# ProPrj_Pocket_bot_2026-03-04.net
KiCad netlist of a schematic drawn in EasyEDA Pro
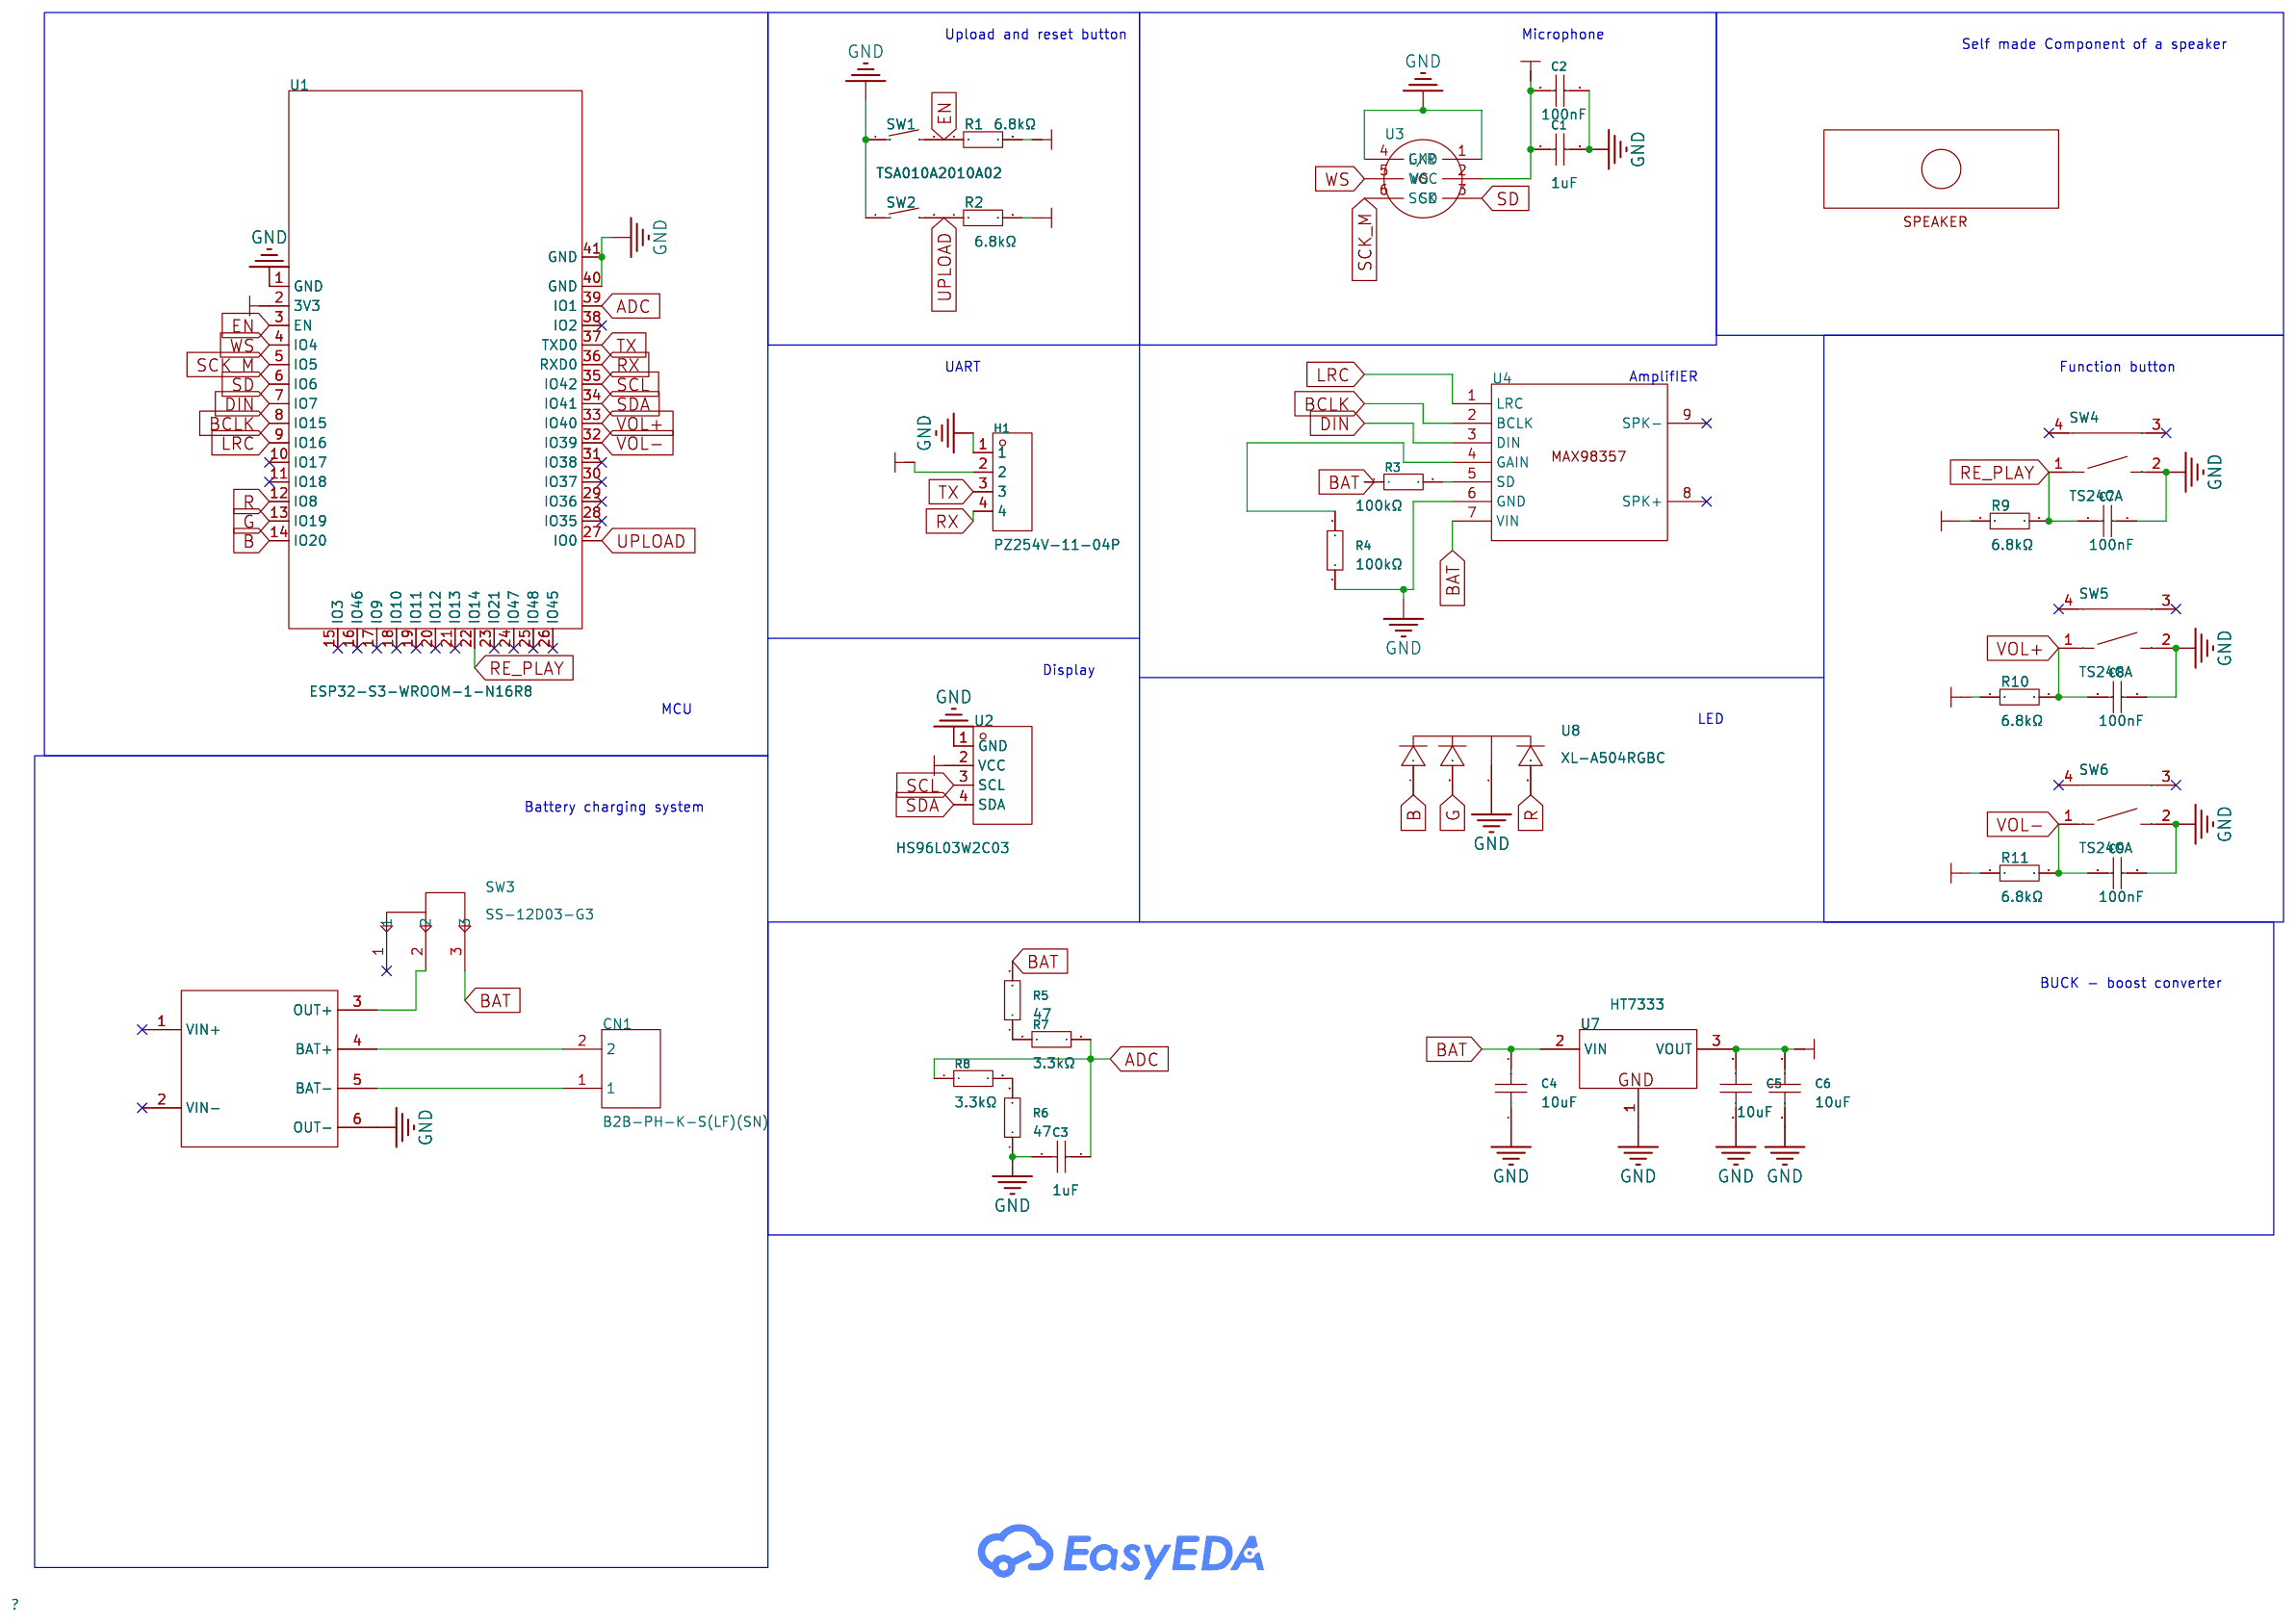
[diagram p0: schematic sheet]

(export (version "E")
  (design (tool "Eeschema 10.0.6"))
  (components
    (comp (ref "C1")
      (value "1uF")
      (footprint "easyedapro:C0805")
      (description "Capacitance:1uF Tolerance:±10% Tolerance:±10% Voltage Rating:50V Temperature Coefficient:X7R")
      (fields
        (field (name "Manufacturer Part") "CL21B105KBFNNNE")
        (field (name "Manufacturer") "SAMSUNG(三星)")
      )
      (libsource (lib "easyedapro") (part "CL21B105KBFNNNE"))
    )
    (comp (ref "C2")
      (value "100nF")
      (footprint "easyedapro:C1206")
      (description "Capacitance:100nF Tolerance:±10% Tolerance:±10% Voltage Rating:50V Temperature Coefficient:X7R")
      (fields
        (field (name "Manufacturer Part") "CL31B104KBCNNNC")
        (field (name "Manufacturer") "SAMSUNG(三星)")
      )
      (libsource (lib "easyedapro") (part "CL31B104KBCNNNC"))
    )
    (comp (ref "C3")
      (value "1uF")
      (footprint "easyedapro:C0805")
      (description "Capacitance:1uF Tolerance:±10% Tolerance:±10% Voltage Rating:50V Temperature Coefficient:X7R")
      (fields
        (field (name "Manufacturer Part") "CL21B105KBFNNNE")
        (field (name "Manufacturer") "SAMSUNG(三星)")
      )
      (libsource (lib "easyedapro") (part "CL21B105KBFNNNE"))
    )
    (comp (ref "C4")
      (value "10uF")
      (footprint "easyedapro:C0603")
      (description "Capacitance:10uF Tolerance:±20% Tolerance:±20% Voltage Rating:25V Temperature Coefficient:X5R")
      (fields
        (field (name "Manufacturer Part") "CL10A106MA8NRNC")
        (field (name "Manufacturer") "SAMSUNG(三星)")
      )
      (libsource (lib "easyedapro") (part "CL10A106MA8NRNC"))
    )
    (comp (ref "C5")
      (value "10uF")
      (footprint "easyedapro:C0603")
      (description "Capacitance:10uF Tolerance:±20% Tolerance:±20% Voltage Rating:25V Temperature Coefficient:X5R")
      (fields
        (field (name "Manufacturer Part") "CL10A106MA8NRNC")
        (field (name "Manufacturer") "SAMSUNG(三星)")
      )
      (libsource (lib "easyedapro") (part "CL10A106MA8NRNC"))
    )
    (comp (ref "C6")
      (value "10uF")
      (footprint "easyedapro:C0603")
      (description "Capacitance:10uF Tolerance:±20% Tolerance:±20% Voltage Rating:25V Temperature Coefficient:X5R")
      (fields
        (field (name "Manufacturer Part") "CL10A106MA8NRNC")
        (field (name "Manufacturer") "SAMSUNG(三星)")
      )
      (libsource (lib "easyedapro") (part "CL10A106MA8NRNC"))
    )
    (comp (ref "C7")
      (value "100nF")
      (footprint "easyedapro:C1206")
      (description "Capacitance:100nF Tolerance:±10% Tolerance:±10% Voltage Rating:50V Temperature Coefficient:X7R")
      (fields
        (field (name "Manufacturer Part") "CL31B104KBCNNNC")
        (field (name "Manufacturer") "SAMSUNG(三星)")
      )
      (libsource (lib "easyedapro") (part "CL31B104KBCNNNC"))
    )
    (comp (ref "C8")
      (value "100nF")
      (footprint "easyedapro:C1206")
      (description "Capacitance:100nF Tolerance:±10% Tolerance:±10% Voltage Rating:50V Temperature Coefficient:X7R")
      (fields
        (field (name "Manufacturer Part") "CL31B104KBCNNNC")
        (field (name "Manufacturer") "SAMSUNG(三星)")
      )
      (libsource (lib "easyedapro") (part "CL31B104KBCNNNC"))
    )
    (comp (ref "C9")
      (value "100nF")
      (footprint "easyedapro:C1206")
      (description "Capacitance:100nF Tolerance:±10% Tolerance:±10% Voltage Rating:50V Temperature Coefficient:X7R")
      (fields
        (field (name "Manufacturer Part") "CL31B104KBCNNNC")
        (field (name "Manufacturer") "SAMSUNG(三星)")
      )
      (libsource (lib "easyedapro") (part "CL31B104KBCNNNC"))
    )
    (comp (ref "CN1")
      (value "B2B-PH-K-S(LF)(SN)")
      (footprint "easyedapro:CONN-TH_B2B-PH-K-S")
      (fields (field (name "Manufacturer") "JST"))
      (libsource (lib "easyedapro") (part "B2B-PH-K-S(LF)(SN)"))
    )
    (comp (ref "H1")
      (value "PZ254V-11-04P")
      (footprint "easyedapro:HDR-TH_4P-P2.54-V-M")
      (fields (field (name "Manufacturer") "XFCN(兴飞)"))
      (libsource (lib "easyedapro") (part "PZ254V-11-04P_C2691448"))
    )
    (comp (ref "R1")
      (value "6.8kΩ")
      (footprint "easyedapro:R0603")
      (fields (field (name "Manufacturer Part") "RC0603FR-071KL") (field (name "Manufacturer") "YAGEO(国巨)"))
      (libsource (lib "easyedapro") (part "RC0603FR-071KL"))
    )
    (comp (ref "R2")
      (value "6.8kΩ")
      (footprint "easyedapro:R0603")
      (fields (field (name "Manufacturer Part") "RC0603FR-071KL") (field (name "Manufacturer") "YAGEO(国巨)"))
      (libsource (lib "easyedapro") (part "RC0603FR-071KL"))
    )
    (comp (ref "R3")
      (value "100kΩ")
      (footprint "easyedapro:R0603")
      (fields (field (name "Manufacturer Part") "RC0603FR-07100KL") (field (name "Manufacturer") "YAGEO(国巨)"))
      (libsource (lib "easyedapro") (part "RC0603FR-07100KL"))
    )
    (comp (ref "R4")
      (value "100kΩ")
      (footprint "easyedapro:R0603")
      (fields (field (name "Manufacturer Part") "RC0603FR-07100KL") (field (name "Manufacturer") "YAGEO(国巨)"))
      (libsource (lib "easyedapro") (part "RC0603FR-07100KL"))
    )
    (comp (ref "R5")
      (value "47")
      (footprint "easyedapro:R1206")
      (fields
        (field (name "Manufacturer Part") "1206W4F100KT5E")
        (field (name "Manufacturer") "UNI-ROYAL(厚声)")
      )
      (libsource (lib "easyedapro") (part "1206W4F100KT5E"))
    )
    (comp (ref "R6")
      (value "47")
      (footprint "easyedapro:R1206")
      (fields
        (field (name "Manufacturer Part") "1206W4F100KT5E")
        (field (name "Manufacturer") "UNI-ROYAL(厚声)")
      )
      (libsource (lib "easyedapro") (part "1206W4F100KT5E"))
    )
    (comp (ref "R7")
      (value "3.3kΩ")
      (footprint "easyedapro:R0603")
      (fields
        (field (name "Manufacturer Part") "0603WAF3301T5E")
        (field (name "Manufacturer") "UNI-ROYAL(厚声)")
      )
      (libsource (lib "easyedapro") (part "0603WAF3301T5E"))
    )
    (comp (ref "R8")
      (value "3.3kΩ")
      (footprint "easyedapro:R0603")
      (fields
        (field (name "Manufacturer Part") "0603WAF3301T5E")
        (field (name "Manufacturer") "UNI-ROYAL(厚声)")
      )
      (libsource (lib "easyedapro") (part "0603WAF3301T5E"))
    )
    (comp (ref "R9")
      (value "6.8kΩ")
      (footprint "easyedapro:R0603")
      (fields (field (name "Manufacturer Part") "RC0603FR-071KL") (field (name "Manufacturer") "YAGEO(国巨)"))
      (libsource (lib "easyedapro") (part "RC0603FR-071KL"))
    )
    (comp (ref "R10")
      (value "6.8kΩ")
      (footprint "easyedapro:R0603")
      (fields (field (name "Manufacturer Part") "RC0603FR-071KL") (field (name "Manufacturer") "YAGEO(国巨)"))
      (libsource (lib "easyedapro") (part "RC0603FR-071KL"))
    )
    (comp (ref "R11")
      (value "6.8kΩ")
      (footprint "easyedapro:R0603")
      (fields (field (name "Manufacturer Part") "RC0603FR-071KL") (field (name "Manufacturer") "YAGEO(国巨)"))
      (libsource (lib "easyedapro") (part "RC0603FR-071KL"))
    )
    (comp (ref "SW1")
      (value "TSA010A2010A02")
      (footprint "easyedapro:KEY-SMD_L3.9-W3.0-LS5.0")
      (fields (field (name "Manufacturer") "BZCN(博众电气)"))
      (libsource (lib "easyedapro") (part "TSA010A2010A02"))
    )
    (comp (ref "SW2")
      (value "TSA010A2010A02")
      (footprint "easyedapro:KEY-SMD_L3.9-W3.0-LS5.0")
      (fields (field (name "Manufacturer") "BZCN(博众电气)"))
      (libsource (lib "easyedapro") (part "TSA010A2010A02"))
    )
    (comp (ref "SW3")
      (value "SS-12D03-G3")
      (footprint "easyedapro:SW-TH_3P-L8.5-W3.5-P2.50_SS-12D03-G3_C5160828")
      (fields (field (name "Manufacturer") "DEALON(德艺隆)"))
      (libsource (lib "easyedapro") (part "SS-12D03-G3_C5160828"))
    )
    (comp (ref "SW4")
      (value "TS24CA")
      (footprint "easyedapro:SW-SMD_2P-TS24CA")
      (fields (field (name "Manufacturer") "SHOU HAN(首韩)"))
      (libsource (lib "easyedapro") (part "TS24CA"))
    )
    (comp (ref "SW5")
      (value "TS24CA")
      (footprint "easyedapro:SW-SMD_2P-TS24CA")
      (fields (field (name "Manufacturer") "SHOU HAN(首韩)"))
      (libsource (lib "easyedapro") (part "TS24CA"))
    )
    (comp (ref "SW6")
      (value "TS24CA")
      (footprint "easyedapro:SW-SMD_2P-TS24CA")
      (fields (field (name "Manufacturer") "SHOU HAN(首韩)"))
      (libsource (lib "easyedapro") (part "TS24CA"))
    )
    (comp (ref "U1")
      (value "ESP32-S3-WROOM-1-N16R8")
      (footprint "easyedapro:WIRELM-SMD_ESP32-S3-WROOM-1")
      (fields (field (name "Manufacturer") "ESPRESSIF(乐鑫)"))
      (libsource (lib "easyedapro") (part "ESP32-S3-WROOM-1(N16R8)"))
    )
    (comp (ref "U2")
      (value "HS96L03W2C03")
      (footprint "easyedapro:OLED-TH_L27.8-W27.2-P2.54_C9900033791")
      (fields (field (name "Manufacturer") "HS(汉昇)"))
      (libsource (lib "easyedapro") (part "HS96L03W2C03"))
    )
    (comp (ref "U3")
      (value "~")
      (footprint "easyedapro:INMP441")
      (libsource (lib "easyedapro") (part "INMP441"))
    )
    (comp (ref "U4")
      (value "~")
      (footprint "easyedapro:MAX98357")
      (libsource (lib "easyedapro") (part "MAX98357"))
    )
    (comp (ref "U5")
      (value "~")
      (footprint "easyedapro:SPEAKER")
      (libsource (lib "easyedapro") (part "SPEAKER"))
    )
    (comp (ref "U6")
      (value "~")
      (footprint "easyedapro:TP4056 Carging Module")
      (libsource (lib "easyedapro") (part "TP4056 Charging Module"))
    )
    (comp (ref "U7")
      (value "HT7333")
      (footprint "easyedapro:SOT-89-3_L4.5-W2.5-P1.50-LS4.1-BR")
      (description "Output Type:-")
      (libsource (lib "easyedapro") (part "HT7333"))
    )
    (comp (ref "U8")
      (value "XL-A504RGBC")
      (footprint "easyedapro:LED-TH_4P-BD5.8-P1.25_DM-50346EH-73826CC-05RGB-BML60-D")
      (fields (field (name "Manufacturer") "XINGLIGHT(成兴光)"))
      (libsource (lib "easyedapro") (part "XL-A504RGBC"))
    )
  )
  (nets
    (net (code "1") (name "+3V3") (class "Default")
      (node (ref "C1") (pin "1") (pinfunction "1_1") (pintype "input"))
      (node (ref "C2") (pin "1") (pinfunction "1_1") (pintype "input"))
      (node (ref "C5") (pin "2") (pinfunction "2_2") (pintype "input"))
      (node (ref "C6") (pin "2") (pinfunction "2_2") (pintype "input"))
      (node (ref "H1") (pin "2") (pinfunction "2_2") (pintype "input"))
      (node (ref "R1") (pin "2") (pinfunction "2_2") (pintype "input"))
      (node (ref "R10") (pin "2") (pinfunction "2_2") (pintype "input"))
      (node (ref "R11") (pin "2") (pinfunction "2_2") (pintype "input"))
      (node (ref "R2") (pin "2") (pinfunction "2_2") (pintype "input"))
      (node (ref "R9") (pin "2") (pinfunction "2_2") (pintype "input"))
      (node (ref "U1") (pin "2") (pinfunction "3V3_2") (pintype "unspecified"))
      (node (ref "U2") (pin "2") (pinfunction "VCC_2") (pintype "unspecified"))
      (node (ref "U3") (pin "2") (pinfunction "VCC_2") (pintype "input"))
      (node (ref "U7") (pin "3") (pinfunction "VOUT_3") (pintype "unspecified"))
    )
    (net (code "2") (name "ADC") (class "Default")
      (node (ref "C3") (pin "2") (pinfunction "2_2") (pintype "input"))
      (node (ref "R7") (pin "2") (pinfunction "2_2") (pintype "input"))
      (node (ref "R8") (pin "1") (pinfunction "1_1") (pintype "input"))
      (node (ref "U1") (pin "39") (pinfunction "IO1_39") (pintype "unspecified"))
    )
    (net (code "3") (name "B") (class "Default")
      (node (ref "U1") (pin "14") (pinfunction "IO20_14") (pintype "unspecified"))
      (node (ref "U8") (pin "4") (pinfunction "4_4") (pintype "unspecified"))
    )
    (net (code "4") (name "BAT") (class "Default")
      (node (ref "C4") (pin "2") (pinfunction "2_2") (pintype "input"))
      (node (ref "R3") (pin "1") (pinfunction "1_1") (pintype "input"))
      (node (ref "R5") (pin "2") (pinfunction "2_2") (pintype "input"))
      (node (ref "SW3") (pin "3") (pinfunction "3_3") (pintype "unspecified"))
      (node (ref "U4") (pin "7") (pinfunction "VIN_7") (pintype "input"))
      (node (ref "U7") (pin "2") (pinfunction "VIN_2") (pintype "unspecified"))
    )
    (net (code "5") (name "BCLK") (class "Default")
      (node (ref "U1") (pin "8") (pinfunction "IO15_8") (pintype "unspecified"))
      (node (ref "U4") (pin "2") (pinfunction "BCLK_2") (pintype "input"))
    )
    (net (code "6") (name "DIN") (class "Default")
      (node (ref "U1") (pin "7") (pinfunction "IO7_7") (pintype "unspecified"))
      (node (ref "U4") (pin "3") (pinfunction "DIN_3") (pintype "input"))
    )
    (net (code "7") (name "EN") (class "Default")
      (node (ref "R1") (pin "1") (pinfunction "1_1") (pintype "input"))
      (node (ref "SW1") (pin "2") (pinfunction "2_2") (pintype "unspecified"))
      (node (ref "U1") (pin "3") (pinfunction "EN_3") (pintype "unspecified"))
    )
    (net (code "8") (name "G") (class "Default")
      (node (ref "U1") (pin "13") (pinfunction "IO19_13") (pintype "unspecified"))
      (node (ref "U8") (pin "3") (pinfunction "3_3") (pintype "unspecified"))
    )
    (net (code "9") (name "GND") (class "Default")
      (node (ref "C1") (pin "2") (pinfunction "2_2") (pintype "input"))
      (node (ref "C2") (pin "2") (pinfunction "2_2") (pintype "input"))
      (node (ref "C3") (pin "1") (pinfunction "1_1") (pintype "input"))
      (node (ref "C4") (pin "1") (pinfunction "1_1") (pintype "input"))
      (node (ref "C5") (pin "1") (pinfunction "1_1") (pintype "input"))
      (node (ref "C6") (pin "1") (pinfunction "1_1") (pintype "input"))
      (node (ref "C7") (pin "2") (pinfunction "2_2") (pintype "input"))
      (node (ref "C8") (pin "2") (pinfunction "2_2") (pintype "input"))
      (node (ref "C9") (pin "2") (pinfunction "2_2") (pintype "input"))
      (node (ref "H1") (pin "1") (pinfunction "1_1") (pintype "input"))
      (node (ref "R4") (pin "1") (pinfunction "1_1") (pintype "input"))
      (node (ref "R6") (pin "1") (pinfunction "1_1") (pintype "input"))
      (node (ref "SW1") (pin "1") (pinfunction "1_1") (pintype "unspecified"))
      (node (ref "SW2") (pin "1") (pinfunction "1_1") (pintype "unspecified"))
      (node (ref "SW4") (pin "2") (pinfunction "2_2") (pintype "unspecified"))
      (node (ref "SW5") (pin "2") (pinfunction "2_2") (pintype "unspecified"))
      (node (ref "SW6") (pin "2") (pinfunction "2_2") (pintype "unspecified"))
      (node (ref "U1") (pin "1") (pinfunction "GND_1") (pintype "unspecified"))
      (node (ref "U1") (pin "40") (pinfunction "GND_40") (pintype "unspecified"))
      (node (ref "U1") (pin "41") (pinfunction "GND_41") (pintype "unspecified"))
      (node (ref "U2") (pin "1") (pinfunction "GND_1") (pintype "unspecified"))
      (node (ref "U3") (pin "1") (pinfunction "GND_1") (pintype "input"))
      (node (ref "U3") (pin "4") (pinfunction "L/R_4") (pintype "input"))
      (node (ref "U4") (pin "6") (pinfunction "GND_6") (pintype "input"))
      (node (ref "U6") (pin "6") (pinfunction "OUT-_6") (pintype "input"))
      (node (ref "U7") (pin "1") (pinfunction "GND_1") (pintype "unspecified"))
      (node (ref "U8") (pin "1") (pinfunction "-_1") (pintype "unspecified"))
    )
    (net (code "10") (name "LRC") (class "Default")
      (node (ref "U1") (pin "9") (pinfunction "IO16_9") (pintype "unspecified"))
      (node (ref "U4") (pin "1") (pinfunction "LRC_1") (pintype "input"))
    )
    (net (code "11") (name "Net-(R5-Pad1)") (class "Default")
      (node (ref "R5") (pin "1") (pinfunction "1_1") (pintype "input"))
      (node (ref "R7") (pin "1") (pinfunction "1_1") (pintype "input"))
    )
    (net (code "12") (name "Net-(R6-Pad2)") (class "Default")
      (node (ref "R6") (pin "2") (pinfunction "2_2") (pintype "input"))
      (node (ref "R8") (pin "2") (pinfunction "2_2") (pintype "input"))
    )
    (net (code "13") (name "Net-(U4-GAIN)") (class "Default")
      (node (ref "R4") (pin "2") (pinfunction "2_2") (pintype "input"))
      (node (ref "U4") (pin "4") (pinfunction "GAIN_4") (pintype "input"))
    )
    (net (code "14") (name "Net-(U4-SD)") (class "Default")
      (node (ref "R3") (pin "2") (pinfunction "2_2") (pintype "input"))
      (node (ref "U4") (pin "5") (pinfunction "SD_5") (pintype "input"))
    )
    (net (code "15") (name "Net-(U6-BAT+)") (class "Default")
      (node (ref "CN1") (pin "2") (pinfunction "2_2") (pintype "input"))
      (node (ref "U6") (pin "4") (pinfunction "BAT+_4") (pintype "input"))
    )
    (net (code "16") (name "Net-(U6-BAT-)") (class "Default")
      (node (ref "CN1") (pin "1") (pinfunction "1_1") (pintype "input"))
      (node (ref "U6") (pin "5") (pinfunction "BAT-_5") (pintype "input"))
    )
    (net (code "17") (name "Net-(U6-OUT+)") (class "Default")
      (node (ref "SW3") (pin "2") (pinfunction "2_2") (pintype "unspecified"))
      (node (ref "U6") (pin "3") (pinfunction "OUT+_3") (pintype "input"))
    )
    (net (code "18") (name "R") (class "Default")
      (node (ref "U1") (pin "12") (pinfunction "IO8_12") (pintype "unspecified"))
      (node (ref "U8") (pin "2") (pinfunction "2_2") (pintype "unspecified"))
    )
    (net (code "19") (name "RE_PLAY") (class "Default")
      (node (ref "C7") (pin "1") (pinfunction "1_1") (pintype "input"))
      (node (ref "R9") (pin "1") (pinfunction "1_1") (pintype "input"))
      (node (ref "SW4") (pin "1") (pinfunction "1_1") (pintype "unspecified"))
      (node (ref "U1") (pin "22") (pinfunction "IO14_22") (pintype "unspecified"))
    )
    (net (code "20") (name "RX") (class "Default")
      (node (ref "H1") (pin "4") (pinfunction "4_4") (pintype "input"))
      (node (ref "U1") (pin "36") (pinfunction "RXD0_36") (pintype "unspecified"))
    )
    (net (code "21") (name "SCK_M") (class "Default")
      (node (ref "U1") (pin "5") (pinfunction "IO5_5") (pintype "unspecified"))
      (node (ref "U3") (pin "6") (pinfunction "SCK_6") (pintype "input"))
    )
    (net (code "22") (name "SCL") (class "Default")
      (node (ref "U1") (pin "35") (pinfunction "IO42_35") (pintype "unspecified"))
      (node (ref "U2") (pin "3") (pinfunction "SCL_3") (pintype "unspecified"))
    )
    (net (code "23") (name "SD") (class "Default")
      (node (ref "U1") (pin "6") (pinfunction "IO6_6") (pintype "unspecified"))
      (node (ref "U3") (pin "3") (pinfunction "SD_3") (pintype "input"))
    )
    (net (code "24") (name "SDA") (class "Default")
      (node (ref "U1") (pin "34") (pinfunction "IO41_34") (pintype "unspecified"))
      (node (ref "U2") (pin "4") (pinfunction "SDA_4") (pintype "unspecified"))
    )
    (net (code "25") (name "TX") (class "Default")
      (node (ref "H1") (pin "3") (pinfunction "3_3") (pintype "input"))
      (node (ref "U1") (pin "37") (pinfunction "TXD0_37") (pintype "unspecified"))
    )
    (net (code "26") (name "UPLOAD") (class "Default")
      (node (ref "R2") (pin "1") (pinfunction "1_1") (pintype "input"))
      (node (ref "SW2") (pin "2") (pinfunction "2_2") (pintype "unspecified"))
      (node (ref "U1") (pin "27") (pinfunction "IO0_27") (pintype "unspecified"))
    )
    (net (code "27") (name "VOL+") (class "Default")
      (node (ref "C8") (pin "1") (pinfunction "1_1") (pintype "input"))
      (node (ref "R10") (pin "1") (pinfunction "1_1") (pintype "input"))
      (node (ref "SW5") (pin "1") (pinfunction "1_1") (pintype "unspecified"))
      (node (ref "U1") (pin "33") (pinfunction "IO40_33") (pintype "unspecified"))
    )
    (net (code "28") (name "VOL-") (class "Default")
      (node (ref "C9") (pin "1") (pinfunction "1_1") (pintype "input"))
      (node (ref "R11") (pin "1") (pinfunction "1_1") (pintype "input"))
      (node (ref "SW6") (pin "1") (pinfunction "1_1") (pintype "unspecified"))
      (node (ref "U1") (pin "32") (pinfunction "IO39_32") (pintype "unspecified"))
    )
    (net (code "29") (name "WS") (class "Default")
      (node (ref "U1") (pin "4") (pinfunction "IO4_4") (pintype "unspecified"))
      (node (ref "U3") (pin "5") (pinfunction "WS_5") (pintype "input"))
    )
    (net (code "30") (name "unconnected-(SW3-Pad1)") (class "Default")
      (node (ref "SW3") (pin "1") (pinfunction "1_1") (pintype "unspecified+no_connect"))
    )
    (net (code "31") (name "unconnected-(SW4-Pad3)") (class "Default")
      (node (ref "SW4") (pin "3") (pinfunction "3_3") (pintype "unspecified+no_connect"))
    )
    (net (code "32") (name "unconnected-(SW4-Pad4)") (class "Default")
      (node (ref "SW4") (pin "4") (pinfunction "4_4") (pintype "unspecified+no_connect"))
    )
    (net (code "33") (name "unconnected-(SW5-Pad3)") (class "Default")
      (node (ref "SW5") (pin "3") (pinfunction "3_3") (pintype "unspecified+no_connect"))
    )
    (net (code "34") (name "unconnected-(SW5-Pad4)") (class "Default")
      (node (ref "SW5") (pin "4") (pinfunction "4_4") (pintype "unspecified+no_connect"))
    )
    (net (code "35") (name "unconnected-(SW6-Pad3)") (class "Default")
      (node (ref "SW6") (pin "3") (pinfunction "3_3") (pintype "unspecified+no_connect"))
    )
    (net (code "36") (name "unconnected-(SW6-Pad4)") (class "Default")
      (node (ref "SW6") (pin "4") (pinfunction "4_4") (pintype "unspecified+no_connect"))
    )
    (net (code "37") (name "unconnected-(U1-IO2-Pad38)") (class "Default")
      (node (ref "U1") (pin "38") (pinfunction "IO2_38") (pintype "unspecified+no_connect"))
    )
    (net (code "38") (name "unconnected-(U1-IO3-Pad15)") (class "Default")
      (node (ref "U1") (pin "15") (pinfunction "IO3_15") (pintype "unspecified+no_connect"))
    )
    (net (code "39") (name "unconnected-(U1-IO9-Pad17)") (class "Default")
      (node (ref "U1") (pin "17") (pinfunction "IO9_17") (pintype "unspecified+no_connect"))
    )
    (net (code "40") (name "unconnected-(U1-IO10-Pad18)") (class "Default")
      (node (ref "U1") (pin "18") (pinfunction "IO10_18") (pintype "unspecified+no_connect"))
    )
    (net (code "41") (name "unconnected-(U1-IO11-Pad19)") (class "Default")
      (node (ref "U1") (pin "19") (pinfunction "IO11_19") (pintype "unspecified+no_connect"))
    )
    (net (code "42") (name "unconnected-(U1-IO12-Pad20)") (class "Default")
      (node (ref "U1") (pin "20") (pinfunction "IO12_20") (pintype "unspecified+no_connect"))
    )
    (net (code "43") (name "unconnected-(U1-IO13-Pad21)") (class "Default")
      (node (ref "U1") (pin "21") (pinfunction "IO13_21") (pintype "unspecified+no_connect"))
    )
    (net (code "44") (name "unconnected-(U1-IO17-Pad10)") (class "Default")
      (node (ref "U1") (pin "10") (pinfunction "IO17_10") (pintype "unspecified+no_connect"))
    )
    (net (code "45") (name "unconnected-(U1-IO18-Pad11)") (class "Default")
      (node (ref "U1") (pin "11") (pinfunction "IO18_11") (pintype "unspecified+no_connect"))
    )
    (net (code "46") (name "unconnected-(U1-IO21-Pad23)") (class "Default")
      (node (ref "U1") (pin "23") (pinfunction "IO21_23") (pintype "unspecified+no_connect"))
    )
    (net (code "47") (name "unconnected-(U1-IO35-Pad28)") (class "Default")
      (node (ref "U1") (pin "28") (pinfunction "IO35_28") (pintype "unspecified+no_connect"))
    )
    (net (code "48") (name "unconnected-(U1-IO36-Pad29)") (class "Default")
      (node (ref "U1") (pin "29") (pinfunction "IO36_29") (pintype "unspecified+no_connect"))
    )
    (net (code "49") (name "unconnected-(U1-IO37-Pad30)") (class "Default")
      (node (ref "U1") (pin "30") (pinfunction "IO37_30") (pintype "unspecified+no_connect"))
    )
    (net (code "50") (name "unconnected-(U1-IO38-Pad31)") (class "Default")
      (node (ref "U1") (pin "31") (pinfunction "IO38_31") (pintype "unspecified+no_connect"))
    )
    (net (code "51") (name "unconnected-(U1-IO45-Pad26)") (class "Default")
      (node (ref "U1") (pin "26") (pinfunction "IO45_26") (pintype "unspecified+no_connect"))
    )
    (net (code "52") (name "unconnected-(U1-IO46-Pad16)") (class "Default")
      (node (ref "U1") (pin "16") (pinfunction "IO46_16") (pintype "unspecified+no_connect"))
    )
    (net (code "53") (name "unconnected-(U1-IO47-Pad24)") (class "Default")
      (node (ref "U1") (pin "24") (pinfunction "IO47_24") (pintype "unspecified+no_connect"))
    )
    (net (code "54") (name "unconnected-(U1-IO48-Pad25)") (class "Default")
      (node (ref "U1") (pin "25") (pinfunction "IO48_25") (pintype "unspecified+no_connect"))
    )
    (net (code "55") (name "unconnected-(U4-SPK+-Pad8)") (class "Default")
      (node (ref "U4") (pin "8") (pinfunction "SPK+_8") (pintype "input+no_connect"))
    )
    (net (code "56") (name "unconnected-(U4-SPK--Pad9)") (class "Default")
      (node (ref "U4") (pin "9") (pinfunction "SPK-_9") (pintype "input+no_connect"))
    )
    (net (code "57") (name "unconnected-(U6-VIN+-Pad1)") (class "Default")
      (node (ref "U6") (pin "1") (pinfunction "VIN+_1") (pintype "input+no_connect"))
    )
    (net (code "58") (name "unconnected-(U6-VIN--Pad2)") (class "Default")
      (node (ref "U6") (pin "2") (pinfunction "VIN-_2") (pintype "input+no_connect"))
    )
  )
)
